# a124-vca.net
KiCad netlist of a schematic drawn in EAGLE
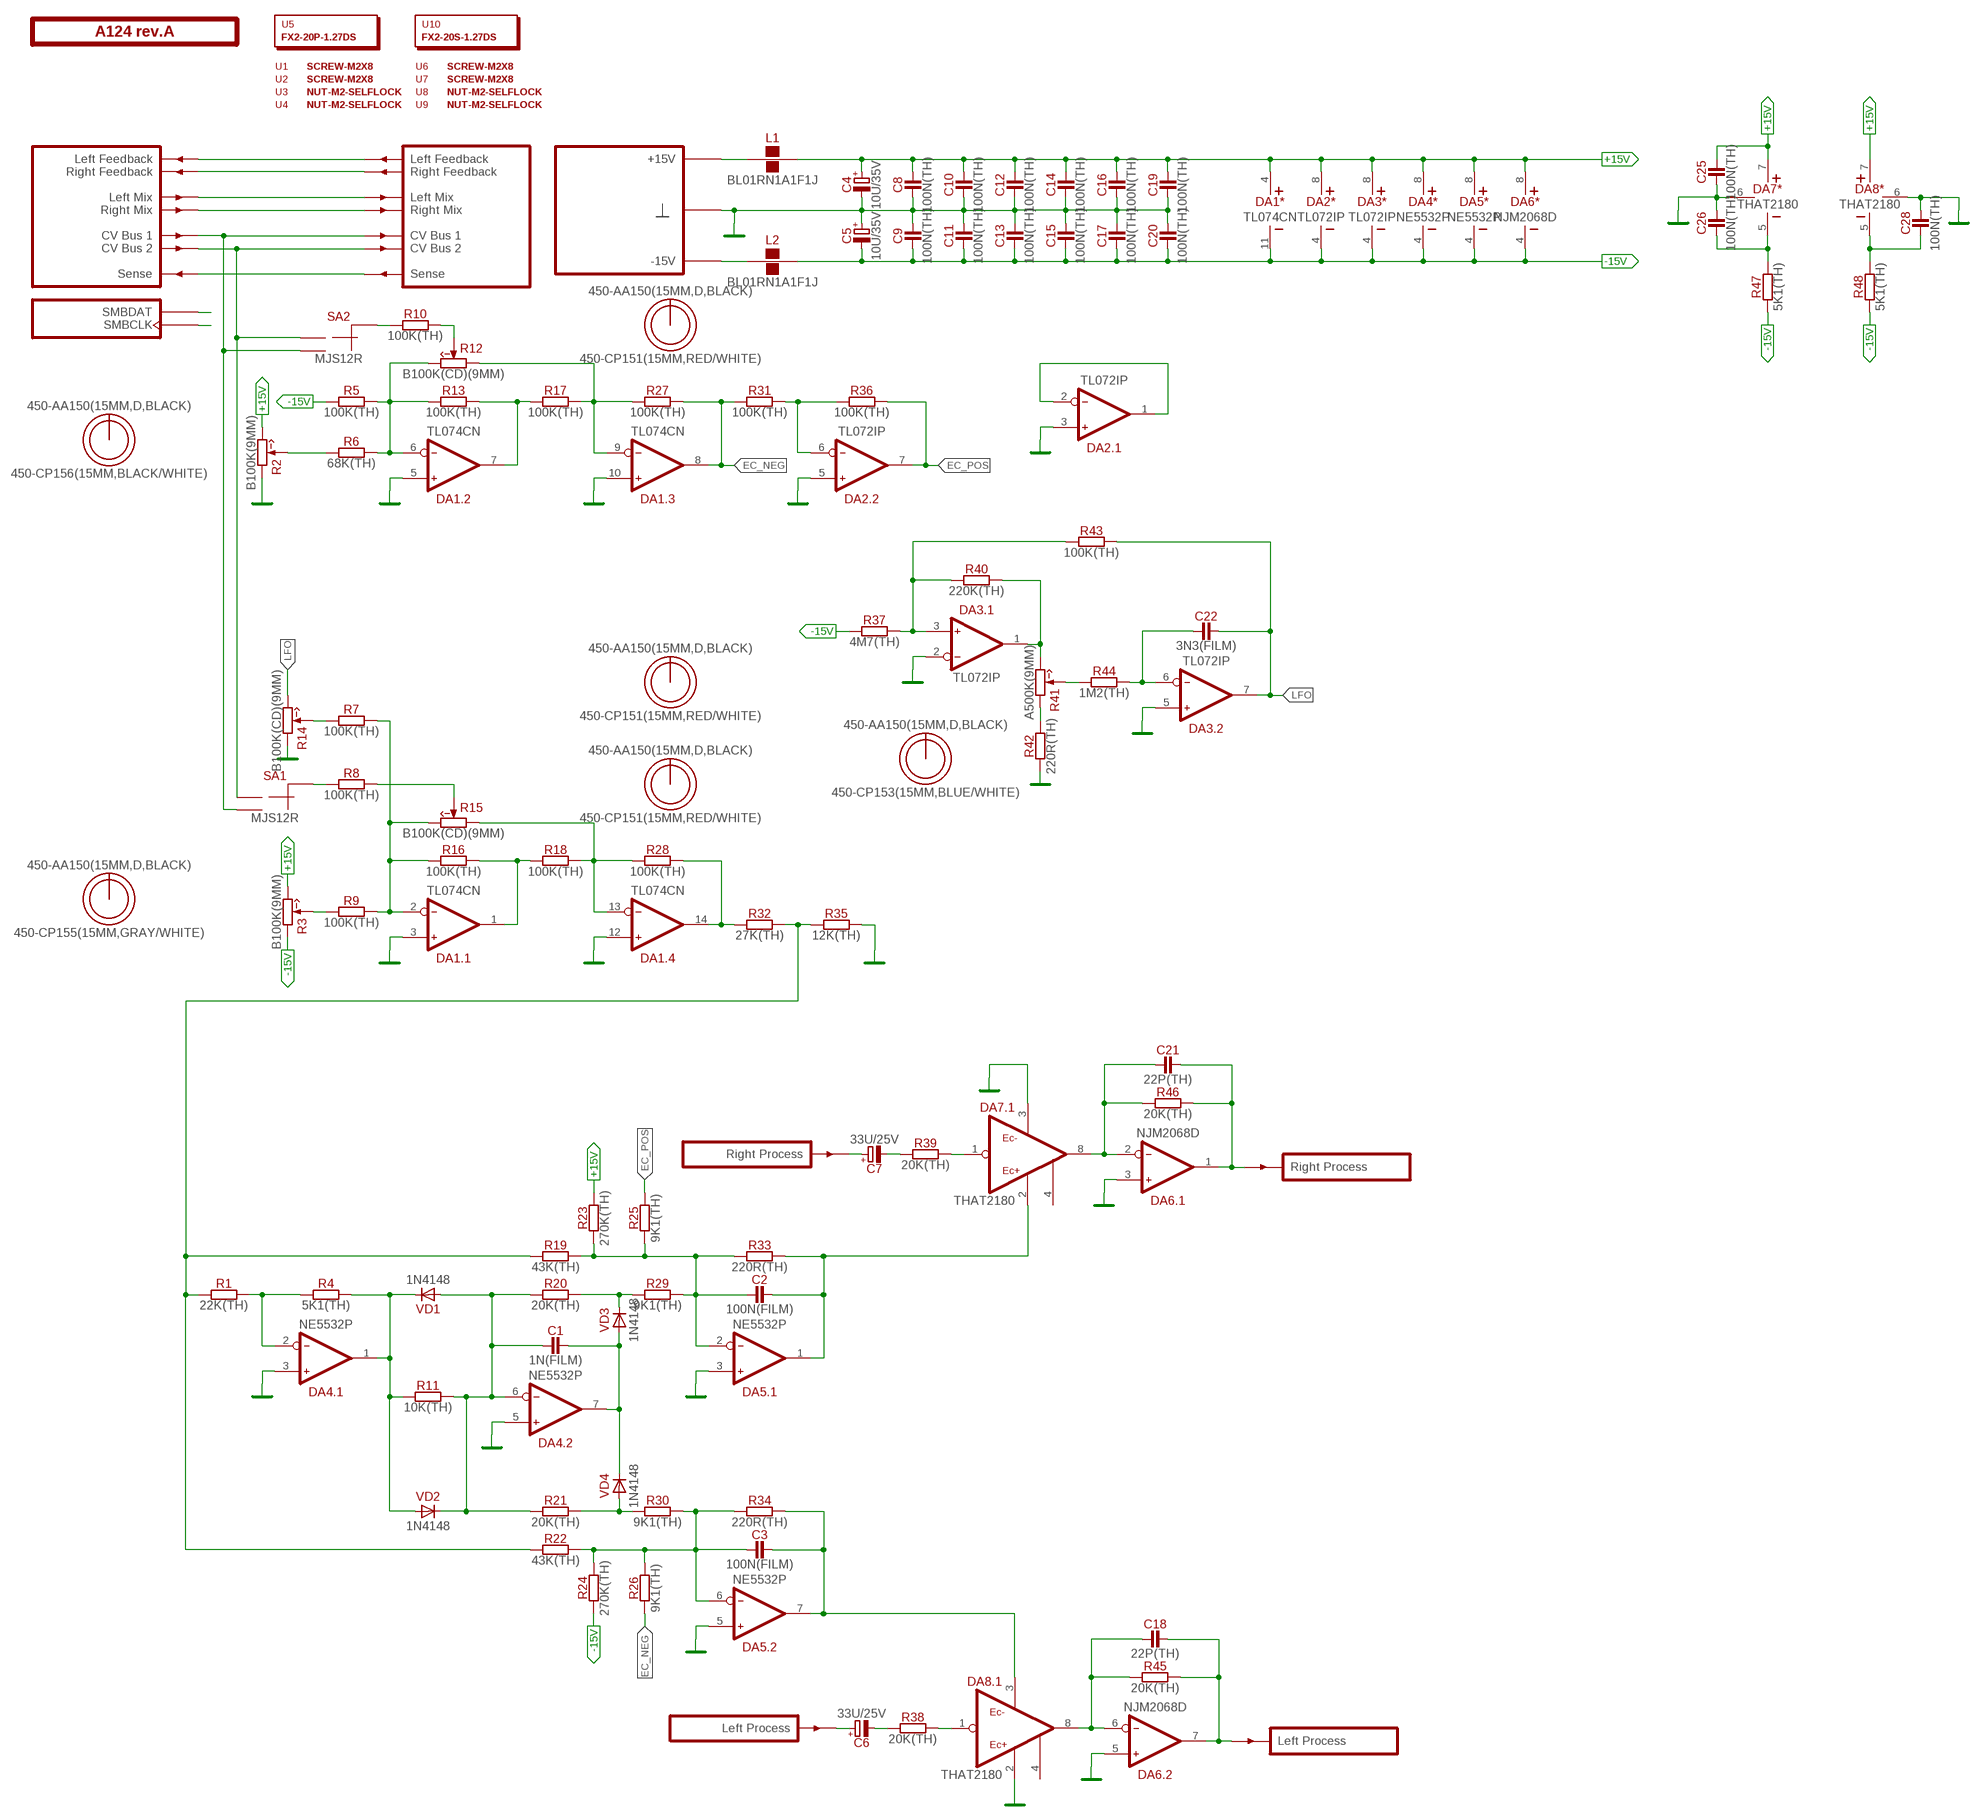
[diagram p0: schematic, sheet 1]

(export (version "E")
  (design (tool "Eeschema 10.0.6"))
  (components
    (comp (ref "C1")
      (value "1N(FILM)")
      (footprint "eagle-import:C050-025X075")
      (libsource (lib "eagle-import") (part "?1N(FILM)"))
    )
    (comp (ref "C2")
      (value "100N(FILM)")
      (footprint "eagle-import:C050-025X075")
      (libsource (lib "eagle-import") (part "?100N(FILM)"))
    )
    (comp (ref "C3")
      (value "100N(FILM)")
      (footprint "eagle-import:C050-025X075")
      (libsource (lib "eagle-import") (part "?100N(FILM)"))
    )
    (comp (ref "C4")
      (value "10U/35V")
      (footprint "eagle-import:E2-5")
      (libsource (lib "eagle-import") (part "?10U/35V"))
    )
    (comp (ref "C5")
      (value "10U/35V")
      (footprint "eagle-import:E2-5")
      (libsource (lib "eagle-import") (part "?10U/35V"))
    )
    (comp (ref "C6")
      (value "33U/25V")
      (footprint "eagle-import:E2,5-7")
      (libsource (lib "eagle-import") (part "?33U/25V"))
    )
    (comp (ref "C7")
      (value "33U/25V")
      (footprint "eagle-import:E2,5-7")
      (libsource (lib "eagle-import") (part "?33U/25V"))
    )
    (comp (ref "C8")
      (value "100N(TH)")
      (footprint "eagle-import:C050-024X044")
      (libsource (lib "eagle-import") (part "?100N(TH)"))
    )
    (comp (ref "C9")
      (value "100N(TH)")
      (footprint "eagle-import:C050-024X044")
      (libsource (lib "eagle-import") (part "?100N(TH)"))
    )
    (comp (ref "C10")
      (value "100N(TH)")
      (footprint "eagle-import:C050-024X044")
      (libsource (lib "eagle-import") (part "?100N(TH)"))
    )
    (comp (ref "C11")
      (value "100N(TH)")
      (footprint "eagle-import:C050-024X044")
      (libsource (lib "eagle-import") (part "?100N(TH)"))
    )
    (comp (ref "C12")
      (value "100N(TH)")
      (footprint "eagle-import:C050-024X044")
      (libsource (lib "eagle-import") (part "?100N(TH)"))
    )
    (comp (ref "C13")
      (value "100N(TH)")
      (footprint "eagle-import:C050-024X044")
      (libsource (lib "eagle-import") (part "?100N(TH)"))
    )
    (comp (ref "C14")
      (value "100N(TH)")
      (footprint "eagle-import:C050-024X044")
      (libsource (lib "eagle-import") (part "?100N(TH)"))
    )
    (comp (ref "C15")
      (value "100N(TH)")
      (footprint "eagle-import:C050-024X044")
      (libsource (lib "eagle-import") (part "?100N(TH)"))
    )
    (comp (ref "C16")
      (value "100N(TH)")
      (footprint "eagle-import:C050-024X044")
      (libsource (lib "eagle-import") (part "?100N(TH)"))
    )
    (comp (ref "C17")
      (value "100N(TH)")
      (footprint "eagle-import:C050-024X044")
      (libsource (lib "eagle-import") (part "?100N(TH)"))
    )
    (comp (ref "C18")
      (value "22P(TH)")
      (footprint "eagle-import:C050-024X044")
      (libsource (lib "eagle-import") (part "?22P(TH)"))
    )
    (comp (ref "C19")
      (value "100N(TH)")
      (footprint "eagle-import:C050-024X044")
      (libsource (lib "eagle-import") (part "?100N(TH)"))
    )
    (comp (ref "C20")
      (value "100N(TH)")
      (footprint "eagle-import:C050-024X044")
      (libsource (lib "eagle-import") (part "?100N(TH)"))
    )
    (comp (ref "C21")
      (value "22P(TH)")
      (footprint "eagle-import:C050-024X044")
      (libsource (lib "eagle-import") (part "?22P(TH)"))
    )
    (comp (ref "C22")
      (value "3N3(FILM)")
      (footprint "eagle-import:C050-025X075")
      (libsource (lib "eagle-import") (part "?3N3(FILM)"))
    )
    (comp (ref "C25")
      (value "100N(TH)")
      (footprint "eagle-import:C050-024X044")
      (libsource (lib "eagle-import") (part "?100N(TH)"))
    )
    (comp (ref "C26")
      (value "100N(TH)")
      (footprint "eagle-import:C050-024X044")
      (libsource (lib "eagle-import") (part "?100N(TH)"))
    )
    (comp (ref "C28")
      (value "100N(TH)")
      (footprint "eagle-import:C050-024X044")
      (libsource (lib "eagle-import") (part "?100N(TH)"))
    )
    (comp (ref "DA1")
      (value "TL074CN")
      (footprint "eagle-import:DIP-14")
      (libsource (lib "eagle-import") (part "TL074CN"))
    )
    (comp (ref "DA2")
      (value "TL072IP")
      (footprint "eagle-import:DIP-8")
      (libsource (lib "eagle-import") (part "TL072IP"))
    )
    (comp (ref "DA3")
      (value "TL072IP")
      (footprint "eagle-import:DIP-8")
      (libsource (lib "eagle-import") (part "TL072IP"))
    )
    (comp (ref "DA4")
      (value "NE5532P")
      (footprint "eagle-import:DIP-8")
      (libsource (lib "eagle-import") (part "NE5532P"))
    )
    (comp (ref "DA5")
      (value "NE5532P")
      (footprint "eagle-import:DIP-8")
      (libsource (lib "eagle-import") (part "NE5532P"))
    )
    (comp (ref "DA6")
      (value "NJM2068D")
      (footprint "eagle-import:DIP-8")
      (libsource (lib "eagle-import") (part "NJM2068D"))
    )
    (comp (ref "DA7")
      (value "THAT2180")
      (footprint "eagle-import:SIL8")
      (libsource (lib "eagle-import") (part "THAT2180"))
    )
    (comp (ref "DA8")
      (value "THAT2180")
      (footprint "eagle-import:SIL8")
      (libsource (lib "eagle-import") (part "THAT2180"))
    )
    (comp (ref "L1")
      (value "BL01RN1A1F1J")
      (footprint "eagle-import:BL01RN1A")
      (libsource (lib "eagle-import") (part "BL01RN1A?1F1J"))
    )
    (comp (ref "L2")
      (value "BL01RN1A1F1J")
      (footprint "eagle-import:BL01RN1A")
      (libsource (lib "eagle-import") (part "BL01RN1A?1F1J"))
    )
    (comp (ref "O1")
      (value "450-AA150(15MM,D,BLACK)")
      (footprint "eagle-import:EMPTY")
      (libsource (lib "eagle-import") (part "450-AA?150(15MM,D,BLACK)"))
    )
    (comp (ref "O2")
      (value "450-CP156(15MM,BLACK/WHITE)")
      (footprint "eagle-import:EMPTY")
      (libsource (lib "eagle-import") (part "450-C?P156(15MM,BLACK/WHITE)"))
    )
    (comp (ref "O3")
      (value "450-AA150(15MM,D,BLACK)")
      (footprint "eagle-import:EMPTY")
      (libsource (lib "eagle-import") (part "450-AA?150(15MM,D,BLACK)"))
    )
    (comp (ref "O4")
      (value "450-CP155(15MM,GRAY/WHITE)")
      (footprint "eagle-import:EMPTY")
      (libsource (lib "eagle-import") (part "450-C?P155(15MM,GRAY/WHITE)"))
    )
    (comp (ref "O5")
      (value "450-AA150(15MM,D,BLACK)")
      (footprint "eagle-import:EMPTY")
      (libsource (lib "eagle-import") (part "450-AA?150(15MM,D,BLACK)"))
    )
    (comp (ref "O6")
      (value "450-CP151(15MM,RED/WHITE)")
      (footprint "eagle-import:EMPTY")
      (libsource (lib "eagle-import") (part "450-C?P151(15MM,RED/WHITE)"))
    )
    (comp (ref "O7")
      (value "450-AA150(15MM,D,BLACK)")
      (footprint "eagle-import:EMPTY")
      (libsource (lib "eagle-import") (part "450-AA?150(15MM,D,BLACK)"))
    )
    (comp (ref "O8")
      (value "450-CP151(15MM,RED/WHITE)")
      (footprint "eagle-import:EMPTY")
      (libsource (lib "eagle-import") (part "450-C?P151(15MM,RED/WHITE)"))
    )
    (comp (ref "O9")
      (value "450-AA150(15MM,D,BLACK)")
      (footprint "eagle-import:EMPTY")
      (libsource (lib "eagle-import") (part "450-AA?150(15MM,D,BLACK)"))
    )
    (comp (ref "O10")
      (value "450-CP151(15MM,RED/WHITE)")
      (footprint "eagle-import:EMPTY")
      (libsource (lib "eagle-import") (part "450-C?P151(15MM,RED/WHITE)"))
    )
    (comp (ref "O11")
      (value "450-AA150(15MM,D,BLACK)")
      (footprint "eagle-import:EMPTY")
      (libsource (lib "eagle-import") (part "450-AA?150(15MM,D,BLACK)"))
    )
    (comp (ref "O12")
      (value "450-CP153(15MM,BLUE/WHITE)")
      (footprint "eagle-import:EMPTY")
      (libsource (lib "eagle-import") (part "450-C?P153(15MM,BLUE/WHITE)"))
    )
    (comp (ref "PCB1")
      (value "A124 rev.A")
      (footprint "eagle-import:ST2-BOARD-74")
      (libsource (lib "eagle-import") (part "ST2-BOARD-?74"))
    )
    (comp (ref "R1")
      (value "22K(TH)")
      (footprint "eagle-import:R-0207_10")
      (libsource (lib "eagle-import") (part "?22K(TH)"))
    )
    (comp (ref "R2")
      (value "B100K(9MM)")
      (footprint "eagle-import:RV09-SINGLE")
      (libsource (lib "eagle-import") (part "?B100K(9MM)"))
    )
    (comp (ref "R3")
      (value "B100K(9MM)")
      (footprint "eagle-import:RV09-SINGLE")
      (libsource (lib "eagle-import") (part "?B100K(9MM)"))
    )
    (comp (ref "R4")
      (value "5K1(TH)")
      (footprint "eagle-import:R-0207_10")
      (libsource (lib "eagle-import") (part "?5K1(TH)"))
    )
    (comp (ref "R5")
      (value "100K(TH)")
      (footprint "eagle-import:R-0207_10")
      (libsource (lib "eagle-import") (part "?100K(TH)"))
    )
    (comp (ref "R6")
      (value "68K(TH)")
      (footprint "eagle-import:R-0207_10")
      (libsource (lib "eagle-import") (part "?68K(TH)"))
    )
    (comp (ref "R7")
      (value "100K(TH)")
      (footprint "eagle-import:R-0207_10")
      (libsource (lib "eagle-import") (part "?100K(TH)"))
    )
    (comp (ref "R8")
      (value "100K(TH)")
      (footprint "eagle-import:R-0207_10")
      (libsource (lib "eagle-import") (part "?100K(TH)"))
    )
    (comp (ref "R9")
      (value "100K(TH)")
      (footprint "eagle-import:R-0207_10")
      (libsource (lib "eagle-import") (part "?100K(TH)"))
    )
    (comp (ref "R10")
      (value "100K(TH)")
      (footprint "eagle-import:R-0207_10")
      (libsource (lib "eagle-import") (part "?100K(TH)"))
    )
    (comp (ref "R11")
      (value "10K(TH)")
      (footprint "eagle-import:R-0207_10")
      (libsource (lib "eagle-import") (part "?10K(TH)"))
    )
    (comp (ref "R12")
      (value "B100K(CD)(9MM)")
      (footprint "eagle-import:RV09-SINGLE")
      (libsource (lib "eagle-import") (part "?B100K(CD)(9MM)"))
    )
    (comp (ref "R13")
      (value "100K(TH)")
      (footprint "eagle-import:R-0207_10")
      (libsource (lib "eagle-import") (part "?100K(TH)"))
    )
    (comp (ref "R14")
      (value "B100K(CD)(9MM)")
      (footprint "eagle-import:RV09-SINGLE")
      (libsource (lib "eagle-import") (part "?B100K(CD)(9MM)"))
    )
    (comp (ref "R15")
      (value "B100K(CD)(9MM)")
      (footprint "eagle-import:RV09-SINGLE")
      (libsource (lib "eagle-import") (part "?B100K(CD)(9MM)"))
    )
    (comp (ref "R16")
      (value "100K(TH)")
      (footprint "eagle-import:R-0207_10")
      (libsource (lib "eagle-import") (part "?100K(TH)"))
    )
    (comp (ref "R17")
      (value "100K(TH)")
      (footprint "eagle-import:R-0207_10")
      (libsource (lib "eagle-import") (part "?100K(TH)"))
    )
    (comp (ref "R18")
      (value "100K(TH)")
      (footprint "eagle-import:R-0207_10")
      (libsource (lib "eagle-import") (part "?100K(TH)"))
    )
    (comp (ref "R19")
      (value "43K(TH)")
      (footprint "eagle-import:R-0207_10")
      (libsource (lib "eagle-import") (part "?43K(TH)"))
    )
    (comp (ref "R20")
      (value "20K(TH)")
      (footprint "eagle-import:R-0207_10")
      (libsource (lib "eagle-import") (part "?20K(TH)"))
    )
    (comp (ref "R21")
      (value "20K(TH)")
      (footprint "eagle-import:R-0207_10")
      (libsource (lib "eagle-import") (part "?20K(TH)"))
    )
    (comp (ref "R22")
      (value "43K(TH)")
      (footprint "eagle-import:R-0207_10")
      (libsource (lib "eagle-import") (part "?43K(TH)"))
    )
    (comp (ref "R23")
      (value "270K(TH)")
      (footprint "eagle-import:R-0207_10")
      (libsource (lib "eagle-import") (part "?270K(TH)"))
    )
    (comp (ref "R24")
      (value "270K(TH)")
      (footprint "eagle-import:R-0207_10")
      (libsource (lib "eagle-import") (part "?270K(TH)"))
    )
    (comp (ref "R25")
      (value "9K1(TH)")
      (footprint "eagle-import:R-0207_10")
      (libsource (lib "eagle-import") (part "?9K1(TH)"))
    )
    (comp (ref "R26")
      (value "9K1(TH)")
      (footprint "eagle-import:R-0207_10")
      (libsource (lib "eagle-import") (part "?9K1(TH)"))
    )
    (comp (ref "R27")
      (value "100K(TH)")
      (footprint "eagle-import:R-0207_10")
      (libsource (lib "eagle-import") (part "?100K(TH)"))
    )
    (comp (ref "R28")
      (value "100K(TH)")
      (footprint "eagle-import:R-0207_10")
      (libsource (lib "eagle-import") (part "?100K(TH)"))
    )
    (comp (ref "R29")
      (value "9K1(TH)")
      (footprint "eagle-import:R-0207_10")
      (libsource (lib "eagle-import") (part "?9K1(TH)"))
    )
    (comp (ref "R30")
      (value "9K1(TH)")
      (footprint "eagle-import:R-0207_10")
      (libsource (lib "eagle-import") (part "?9K1(TH)"))
    )
    (comp (ref "R31")
      (value "100K(TH)")
      (footprint "eagle-import:R-0207_10")
      (libsource (lib "eagle-import") (part "?100K(TH)"))
    )
    (comp (ref "R32")
      (value "27K(TH)")
      (footprint "eagle-import:R-0207_10")
      (libsource (lib "eagle-import") (part "?27K(TH)"))
    )
    (comp (ref "R33")
      (value "220R(TH)")
      (footprint "eagle-import:R-0207_10")
      (libsource (lib "eagle-import") (part "?220R(TH)"))
    )
    (comp (ref "R34")
      (value "220R(TH)")
      (footprint "eagle-import:R-0207_10")
      (libsource (lib "eagle-import") (part "?220R(TH)"))
    )
    (comp (ref "R35")
      (value "12K(TH)")
      (footprint "eagle-import:R-0207_10")
      (libsource (lib "eagle-import") (part "?12K(TH)"))
    )
    (comp (ref "R36")
      (value "100K(TH)")
      (footprint "eagle-import:R-0207_10")
      (libsource (lib "eagle-import") (part "?100K(TH)"))
    )
    (comp (ref "R37")
      (value "4M7(TH)")
      (footprint "eagle-import:R-0207_10")
      (libsource (lib "eagle-import") (part "?4M7(TH)"))
    )
    (comp (ref "R38")
      (value "20K(TH)")
      (footprint "eagle-import:R-0207_10")
      (libsource (lib "eagle-import") (part "?20K(TH)"))
    )
    (comp (ref "R39")
      (value "20K(TH)")
      (footprint "eagle-import:R-0207_10")
      (libsource (lib "eagle-import") (part "?20K(TH)"))
    )
    (comp (ref "R40")
      (value "220K(TH)")
      (footprint "eagle-import:R-0207_10")
      (libsource (lib "eagle-import") (part "?220K(TH)"))
    )
    (comp (ref "R41")
      (value "A500K(9MM)")
      (footprint "eagle-import:RV09-SINGLE")
      (libsource (lib "eagle-import") (part "?A500K(9MM)"))
    )
    (comp (ref "R42")
      (value "220R(TH)")
      (footprint "eagle-import:R-0207_10")
      (libsource (lib "eagle-import") (part "?220R(TH)"))
    )
    (comp (ref "R43")
      (value "100K(TH)")
      (footprint "eagle-import:R-0207_10")
      (libsource (lib "eagle-import") (part "?100K(TH)"))
    )
    (comp (ref "R44")
      (value "1M2(TH)")
      (footprint "eagle-import:R-0207_10")
      (libsource (lib "eagle-import") (part "?1M2(TH)"))
    )
    (comp (ref "R45")
      (value "20K(TH)")
      (footprint "eagle-import:R-0207_10")
      (libsource (lib "eagle-import") (part "?20K(TH)"))
    )
    (comp (ref "R46")
      (value "20K(TH)")
      (footprint "eagle-import:R-0207_10")
      (libsource (lib "eagle-import") (part "?20K(TH)"))
    )
    (comp (ref "R47")
      (value "5K1(TH)")
      (footprint "eagle-import:R-0207_10")
      (libsource (lib "eagle-import") (part "?5K1(TH)"))
    )
    (comp (ref "R48")
      (value "5K1(TH)")
      (footprint "eagle-import:R-0207_10")
      (libsource (lib "eagle-import") (part "?5K1(TH)"))
    )
    (comp (ref "SA1")
      (value "MJS12R")
      (footprint "eagle-import:APEM-MJS12R")
      (libsource (lib "eagle-import") (part "MJS12R"))
    )
    (comp (ref "SA2")
      (value "MJS12R")
      (footprint "eagle-import:APEM-MJS12R")
      (libsource (lib "eagle-import") (part "MJS12R"))
    )
    (comp (ref "U1")
      (value "SCREW-M2X8")
      (footprint "eagle-import:EMPTY")
      (libsource (lib "eagle-import") (part "?SCREW-M2X8"))
    )
    (comp (ref "U2")
      (value "SCREW-M2X8")
      (footprint "eagle-import:EMPTY")
      (libsource (lib "eagle-import") (part "?SCREW-M2X8"))
    )
    (comp (ref "U3")
      (value "NUT-M2-SELFLOCK")
      (footprint "eagle-import:EMPTY")
      (libsource (lib "eagle-import") (part "?NUT-M2-SELFLOCK"))
    )
    (comp (ref "U4")
      (value "NUT-M2-SELFLOCK")
      (footprint "eagle-import:EMPTY")
      (libsource (lib "eagle-import") (part "?NUT-M2-SELFLOCK"))
    )
    (comp (ref "U5")
      (value "FX2-20P-1.27DS")
      (footprint "eagle-import:EMPTY")
      (libsource (lib "eagle-import") (part "?FX2-20P-1.27DS"))
    )
    (comp (ref "U6")
      (value "SCREW-M2X8")
      (footprint "eagle-import:EMPTY")
      (libsource (lib "eagle-import") (part "?SCREW-M2X8"))
    )
    (comp (ref "U7")
      (value "SCREW-M2X8")
      (footprint "eagle-import:EMPTY")
      (libsource (lib "eagle-import") (part "?SCREW-M2X8"))
    )
    (comp (ref "U8")
      (value "NUT-M2-SELFLOCK")
      (footprint "eagle-import:EMPTY")
      (libsource (lib "eagle-import") (part "?NUT-M2-SELFLOCK"))
    )
    (comp (ref "U9")
      (value "NUT-M2-SELFLOCK")
      (footprint "eagle-import:EMPTY")
      (libsource (lib "eagle-import") (part "?NUT-M2-SELFLOCK"))
    )
    (comp (ref "U10")
      (value "FX2-20S-1.27DS")
      (footprint "eagle-import:EMPTY")
      (libsource (lib "eagle-import") (part "?FX2-20S-1.27DS"))
    )
    (comp (ref "VD1")
      (value "1N4148")
      (footprint "eagle-import:DO35-7")
      (libsource (lib "eagle-import") (part "?1N4148"))
    )
    (comp (ref "VD2")
      (value "1N4148")
      (footprint "eagle-import:DO35-7")
      (libsource (lib "eagle-import") (part "?1N4148"))
    )
    (comp (ref "VD3")
      (value "1N4148")
      (footprint "eagle-import:DO35-7")
      (libsource (lib "eagle-import") (part "?1N4148"))
    )
    (comp (ref "VD4")
      (value "1N4148")
      (footprint "eagle-import:DO35-7")
      (libsource (lib "eagle-import") (part "?1N4148"))
    )
  )
  (nets
    (net (code "1") (name "+15V") (class "Default")
      (node (ref "C10") (pin "2") (pinfunction "2_2") (pintype "passive"))
      (node (ref "C12") (pin "2") (pinfunction "2_2") (pintype "passive"))
      (node (ref "C14") (pin "2") (pinfunction "2_2") (pintype "passive"))
      (node (ref "C16") (pin "2") (pinfunction "2_2") (pintype "passive"))
      (node (ref "C19") (pin "2") (pinfunction "2_2") (pintype "passive"))
      (node (ref "C25") (pin "2") (pinfunction "2_2") (pintype "passive"))
      (node (ref "C4") (pin "+") (pinfunction "+_+") (pintype "passive"))
      (node (ref "C8") (pin "2") (pinfunction "2_2") (pintype "passive"))
      (node (ref "DA1") (pin "4") (pinfunction "V+_4") (pintype "power_in"))
      (node (ref "DA2") (pin "8") (pinfunction "V+_8") (pintype "power_in"))
      (node (ref "DA3") (pin "8") (pinfunction "V+_8") (pintype "power_in"))
      (node (ref "DA4") (pin "8") (pinfunction "V+_8") (pintype "power_in"))
      (node (ref "DA5") (pin "8") (pinfunction "V+_8") (pintype "power_in"))
      (node (ref "DA6") (pin "8") (pinfunction "V+_8") (pintype "power_in"))
      (node (ref "DA7") (pin "7") (pinfunction "V+_7") (pintype "power_in"))
      (node (ref "DA8") (pin "7") (pinfunction "V+_7") (pintype "power_in"))
      (node (ref "L1") (pin "2") (pinfunction "2_2") (pintype "passive"))
      (node (ref "R2") (pin "3") (pinfunction "CW_3") (pintype "passive"))
      (node (ref "R23") (pin "2") (pinfunction "2_2") (pintype "passive"))
      (node (ref "R3") (pin "3") (pinfunction "CW_3") (pintype "passive"))
    )
    (net (code "2") (name "-15V") (class "Default")
      (node (ref "C11") (pin "1") (pinfunction "1_1") (pintype "passive"))
      (node (ref "C13") (pin "1") (pinfunction "1_1") (pintype "passive"))
      (node (ref "C15") (pin "1") (pinfunction "1_1") (pintype "passive"))
      (node (ref "C17") (pin "1") (pinfunction "1_1") (pintype "passive"))
      (node (ref "C20") (pin "1") (pinfunction "1_1") (pintype "passive"))
      (node (ref "C5") (pin "-") (pinfunction "-_-") (pintype "passive"))
      (node (ref "C9") (pin "1") (pinfunction "1_1") (pintype "passive"))
      (node (ref "DA1") (pin "11") (pinfunction "V-_11") (pintype "power_in"))
      (node (ref "DA2") (pin "4") (pinfunction "V-_4") (pintype "power_in"))
      (node (ref "DA3") (pin "4") (pinfunction "V-_4") (pintype "power_in"))
      (node (ref "DA4") (pin "4") (pinfunction "V-_4") (pintype "power_in"))
      (node (ref "DA5") (pin "4") (pinfunction "V-_4") (pintype "power_in"))
      (node (ref "DA6") (pin "4") (pinfunction "V-_4") (pintype "power_in"))
      (node (ref "L2") (pin "2") (pinfunction "2_2") (pintype "passive"))
      (node (ref "R24") (pin "1") (pinfunction "1_1") (pintype "passive"))
      (node (ref "R3") (pin "1") (pinfunction "CCW_1") (pintype "passive"))
      (node (ref "R37") (pin "1") (pinfunction "1_1") (pintype "passive"))
      (node (ref "R47") (pin "1") (pinfunction "1_1") (pintype "passive"))
      (node (ref "R48") (pin "1") (pinfunction "1_1") (pintype "passive"))
      (node (ref "R5") (pin "1") (pinfunction "1_1") (pintype "passive"))
    )
    (net (code "3") (name "EC_NEG") (class "Default")
      (node (ref "DA1") (pin "8") (pinfunction "OUT_8") (pintype "output"))
      (node (ref "R26") (pin "1") (pinfunction "1_1") (pintype "passive"))
      (node (ref "R27") (pin "2") (pinfunction "2_2") (pintype "passive"))
      (node (ref "R31") (pin "1") (pinfunction "1_1") (pintype "passive"))
    )
    (net (code "4") (name "EC_POS") (class "Default")
      (node (ref "DA2") (pin "7") (pinfunction "OUT_7") (pintype "output"))
      (node (ref "R25") (pin "2") (pinfunction "2_2") (pintype "passive"))
      (node (ref "R36") (pin "2") (pinfunction "2_2") (pintype "passive"))
    )
    (net (code "5") (name "GND") (class "Default")
      (node (ref "C10") (pin "1") (pinfunction "1_1") (pintype "passive"))
      (node (ref "C11") (pin "2") (pinfunction "2_2") (pintype "passive"))
      (node (ref "C12") (pin "1") (pinfunction "1_1") (pintype "passive"))
      (node (ref "C13") (pin "2") (pinfunction "2_2") (pintype "passive"))
      (node (ref "C14") (pin "1") (pinfunction "1_1") (pintype "passive"))
      (node (ref "C15") (pin "2") (pinfunction "2_2") (pintype "passive"))
      (node (ref "C16") (pin "1") (pinfunction "1_1") (pintype "passive"))
      (node (ref "C17") (pin "2") (pinfunction "2_2") (pintype "passive"))
      (node (ref "C19") (pin "1") (pinfunction "1_1") (pintype "passive"))
      (node (ref "C20") (pin "2") (pinfunction "2_2") (pintype "passive"))
      (node (ref "C25") (pin "1") (pinfunction "1_1") (pintype "passive"))
      (node (ref "C26") (pin "2") (pinfunction "2_2") (pintype "passive"))
      (node (ref "C28") (pin "2") (pinfunction "2_2") (pintype "passive"))
      (node (ref "C4") (pin "-") (pinfunction "-_-") (pintype "passive"))
      (node (ref "C5") (pin "+") (pinfunction "+_+") (pintype "passive"))
      (node (ref "C8") (pin "1") (pinfunction "1_1") (pintype "passive"))
      (node (ref "C9") (pin "2") (pinfunction "2_2") (pintype "passive"))
      (node (ref "DA1") (pin "10") (pinfunction "IN+_10") (pintype "input"))
      (node (ref "DA1") (pin "12") (pinfunction "IN+_12") (pintype "input"))
      (node (ref "DA1") (pin "3") (pinfunction "IN+_3") (pintype "input"))
      (node (ref "DA1") (pin "5") (pinfunction "IN+_5") (pintype "input"))
      (node (ref "DA2") (pin "3") (pinfunction "IN+_3") (pintype "input"))
      (node (ref "DA2") (pin "5") (pinfunction "IN+_5") (pintype "input"))
      (node (ref "DA3") (pin "2") (pinfunction "IN-_2") (pintype "input"))
      (node (ref "DA3") (pin "5") (pinfunction "IN+_5") (pintype "input"))
      (node (ref "DA4") (pin "3") (pinfunction "IN+_3") (pintype "input"))
      (node (ref "DA4") (pin "5") (pinfunction "IN+_5") (pintype "input"))
      (node (ref "DA5") (pin "3") (pinfunction "IN+_3") (pintype "input"))
      (node (ref "DA5") (pin "5") (pinfunction "IN+_5") (pintype "input"))
      (node (ref "DA6") (pin "3") (pinfunction "IN+_3") (pintype "input"))
      (node (ref "DA6") (pin "5") (pinfunction "IN+_5") (pintype "input"))
      (node (ref "DA7") (pin "3") (pinfunction "EC-_3") (pintype "output"))
      (node (ref "DA7") (pin "6") (pinfunction "GND_6") (pintype "power_in"))
      (node (ref "DA8") (pin "2") (pinfunction "EC+_2") (pintype "output"))
      (node (ref "DA8") (pin "6") (pinfunction "GND_6") (pintype "power_in"))
      (node (ref "PCB1") (pin "B4") (pinfunction "GND_B4") (pintype "bidirectional"))
      (node (ref "PCB1") (pin "B4'") (pinfunction "GND_B4'") (pintype "bidirectional"))
      (node (ref "PCB1") (pin "B5") (pinfunction "GND_B5") (pintype "bidirectional"))
      (node (ref "PCB1") (pin "B5'") (pinfunction "GND_B5'") (pintype "bidirectional"))
      (node (ref "PCB1") (pin "B6") (pinfunction "GND_B6") (pintype "bidirectional"))
      (node (ref "PCB1") (pin "B6'") (pinfunction "GND_B6'") (pintype "bidirectional"))
      (node (ref "PCB1") (pin "B7") (pinfunction "GND_B7") (pintype "bidirectional"))
      (node (ref "PCB1") (pin "B7'") (pinfunction "GND_B7'") (pintype "bidirectional"))
      (node (ref "PCB1") (pin "B8") (pinfunction "GND_B8") (pintype "bidirectional"))
      (node (ref "PCB1") (pin "B8'") (pinfunction "GND_B8'") (pintype "bidirectional"))
      (node (ref "R14") (pin "1") (pinfunction "CCW_1") (pintype "passive"))
      (node (ref "R2") (pin "1") (pinfunction "CCW_1") (pintype "passive"))
      (node (ref "R35") (pin "2") (pinfunction "2_2") (pintype "passive"))
      (node (ref "R42") (pin "1") (pinfunction "1_1") (pintype "passive"))
    )
    (net (code "6") (name "LFO") (class "Default")
      (node (ref "C22") (pin "2") (pinfunction "2_2") (pintype "passive"))
      (node (ref "DA3") (pin "7") (pinfunction "OUT_7") (pintype "output"))
      (node (ref "R14") (pin "3") (pinfunction "CW_3") (pintype "passive"))
      (node (ref "R43") (pin "2") (pinfunction "2_2") (pintype "passive"))
    )
    (net (code "7") (name "Net-(C6-Pad-)") (class "Default")
      (node (ref "C6") (pin "-") (pinfunction "-_-") (pintype "passive"))
      (node (ref "R38") (pin "1") (pinfunction "1_1") (pintype "passive"))
    )
    (net (code "8") (name "Net-(C7-Pad-)") (class "Default")
      (node (ref "C7") (pin "-") (pinfunction "-_-") (pintype "passive"))
      (node (ref "R39") (pin "1") (pinfunction "1_1") (pintype "passive"))
    )
    (net (code "9") (name "Net-(DA1B-IN-)") (class "Default")
      (node (ref "DA1") (pin "2") (pinfunction "IN-_2") (pintype "input"))
      (node (ref "R15") (pin "3") (pinfunction "CW_3") (pintype "passive"))
      (node (ref "R16") (pin "1") (pinfunction "1_1") (pintype "passive"))
      (node (ref "R7") (pin "2") (pinfunction "2_2") (pintype "passive"))
      (node (ref "R9") (pin "2") (pinfunction "2_2") (pintype "passive"))
    )
    (net (code "10") (name "Net-(DA1B-OUT)") (class "Default")
      (node (ref "DA1") (pin "1") (pinfunction "OUT_1") (pintype "output"))
      (node (ref "R16") (pin "2") (pinfunction "2_2") (pintype "passive"))
      (node (ref "R18") (pin "1") (pinfunction "1_1") (pintype "passive"))
    )
    (net (code "11") (name "Net-(DA1C-IN-)") (class "Default")
      (node (ref "DA1") (pin "6") (pinfunction "IN-_6") (pintype "input"))
      (node (ref "R12") (pin "3") (pinfunction "CW_3") (pintype "passive"))
      (node (ref "R13") (pin "1") (pinfunction "1_1") (pintype "passive"))
      (node (ref "R5") (pin "2") (pinfunction "2_2") (pintype "passive"))
      (node (ref "R6") (pin "2") (pinfunction "2_2") (pintype "passive"))
    )
    (net (code "12") (name "Net-(DA1C-OUT)") (class "Default")
      (node (ref "DA1") (pin "7") (pinfunction "OUT_7") (pintype "output"))
      (node (ref "R13") (pin "2") (pinfunction "2_2") (pintype "passive"))
      (node (ref "R17") (pin "1") (pinfunction "1_1") (pintype "passive"))
    )
    (net (code "13") (name "Net-(DA1D-IN-)") (class "Default")
      (node (ref "DA1") (pin "9") (pinfunction "IN-_9") (pintype "input"))
      (node (ref "R12") (pin "1") (pinfunction "CCW_1") (pintype "passive"))
      (node (ref "R17") (pin "2") (pinfunction "2_2") (pintype "passive"))
      (node (ref "R27") (pin "1") (pinfunction "1_1") (pintype "passive"))
    )
    (net (code "14") (name "Net-(DA1E-IN-)") (class "Default")
      (node (ref "DA1") (pin "13") (pinfunction "IN-_13") (pintype "input"))
      (node (ref "R15") (pin "1") (pinfunction "CCW_1") (pintype "passive"))
      (node (ref "R18") (pin "2") (pinfunction "2_2") (pintype "passive"))
      (node (ref "R28") (pin "1") (pinfunction "1_1") (pintype "passive"))
    )
    (net (code "15") (name "Net-(DA1E-OUT)") (class "Default")
      (node (ref "DA1") (pin "14") (pinfunction "OUT_14") (pintype "output"))
      (node (ref "R28") (pin "2") (pinfunction "2_2") (pintype "passive"))
      (node (ref "R32") (pin "1") (pinfunction "1_1") (pintype "passive"))
    )
    (net (code "16") (name "Net-(DA2B-IN-)") (class "Default")
      (node (ref "DA2") (pin "1") (pinfunction "OUT_1") (pintype "output"))
      (node (ref "DA2") (pin "2") (pinfunction "IN-_2") (pintype "input"))
    )
    (net (code "17") (name "Net-(DA2C-IN-)") (class "Default")
      (node (ref "DA2") (pin "6") (pinfunction "IN-_6") (pintype "input"))
      (node (ref "R31") (pin "2") (pinfunction "2_2") (pintype "passive"))
      (node (ref "R36") (pin "1") (pinfunction "1_1") (pintype "passive"))
    )
    (net (code "18") (name "Net-(DA3B-IN+)") (class "Default")
      (node (ref "DA3") (pin "3") (pinfunction "IN+_3") (pintype "input"))
      (node (ref "R37") (pin "2") (pinfunction "2_2") (pintype "passive"))
      (node (ref "R40") (pin "1") (pinfunction "1_1") (pintype "passive"))
      (node (ref "R43") (pin "1") (pinfunction "1_1") (pintype "passive"))
    )
    (net (code "19") (name "Net-(DA3B-OUT)") (class "Default")
      (node (ref "DA3") (pin "1") (pinfunction "OUT_1") (pintype "output"))
      (node (ref "R40") (pin "2") (pinfunction "2_2") (pintype "passive"))
      (node (ref "R41") (pin "3") (pinfunction "CW_3") (pintype "passive"))
    )
    (net (code "20") (name "Net-(DA3C-IN-)") (class "Default")
      (node (ref "C22") (pin "1") (pinfunction "1_1") (pintype "passive"))
      (node (ref "DA3") (pin "6") (pinfunction "IN-_6") (pintype "input"))
      (node (ref "R44") (pin "2") (pinfunction "2_2") (pintype "passive"))
    )
    (net (code "21") (name "Net-(DA4B-IN-)") (class "Default")
      (node (ref "DA4") (pin "2") (pinfunction "IN-_2") (pintype "input"))
      (node (ref "R1") (pin "2") (pinfunction "2_2") (pintype "passive"))
      (node (ref "R4") (pin "1") (pinfunction "1_1") (pintype "passive"))
    )
    (net (code "22") (name "Net-(DA4B-OUT)") (class "Default")
      (node (ref "DA4") (pin "1") (pinfunction "OUT_1") (pintype "output"))
      (node (ref "R11") (pin "1") (pinfunction "1_1") (pintype "passive"))
      (node (ref "R4") (pin "2") (pinfunction "2_2") (pintype "passive"))
      (node (ref "VD1") (pin "C") (pinfunction "C_C") (pintype "passive"))
      (node (ref "VD2") (pin "A") (pinfunction "A_A") (pintype "passive"))
    )
    (net (code "23") (name "Net-(DA4C-IN-)") (class "Default")
      (node (ref "C1") (pin "1") (pinfunction "1_1") (pintype "passive"))
      (node (ref "DA4") (pin "6") (pinfunction "IN-_6") (pintype "input"))
      (node (ref "R11") (pin "2") (pinfunction "2_2") (pintype "passive"))
      (node (ref "R20") (pin "1") (pinfunction "1_1") (pintype "passive"))
      (node (ref "R21") (pin "1") (pinfunction "1_1") (pintype "passive"))
      (node (ref "VD1") (pin "A") (pinfunction "A_A") (pintype "passive"))
      (node (ref "VD2") (pin "C") (pinfunction "C_C") (pintype "passive"))
    )
    (net (code "24") (name "Net-(DA4C-OUT)") (class "Default")
      (node (ref "C1") (pin "2") (pinfunction "2_2") (pintype "passive"))
      (node (ref "DA4") (pin "7") (pinfunction "OUT_7") (pintype "output"))
      (node (ref "VD3") (pin "A") (pinfunction "A_A") (pintype "passive"))
      (node (ref "VD4") (pin "C") (pinfunction "C_C") (pintype "passive"))
    )
    (net (code "25") (name "Net-(DA5B-IN-)") (class "Default")
      (node (ref "C2") (pin "1") (pinfunction "1_1") (pintype "passive"))
      (node (ref "DA5") (pin "2") (pinfunction "IN-_2") (pintype "input"))
      (node (ref "R19") (pin "2") (pinfunction "2_2") (pintype "passive"))
      (node (ref "R23") (pin "1") (pinfunction "1_1") (pintype "passive"))
      (node (ref "R25") (pin "1") (pinfunction "1_1") (pintype "passive"))
      (node (ref "R29") (pin "2") (pinfunction "2_2") (pintype "passive"))
      (node (ref "R33") (pin "1") (pinfunction "1_1") (pintype "passive"))
    )
    (net (code "26") (name "Net-(DA5B-OUT)") (class "Default")
      (node (ref "C2") (pin "2") (pinfunction "2_2") (pintype "passive"))
      (node (ref "DA5") (pin "1") (pinfunction "OUT_1") (pintype "output"))
      (node (ref "DA7") (pin "2") (pinfunction "EC+_2") (pintype "output"))
      (node (ref "R33") (pin "2") (pinfunction "2_2") (pintype "passive"))
    )
    (net (code "27") (name "Net-(DA5C-IN-)") (class "Default")
      (node (ref "C3") (pin "1") (pinfunction "1_1") (pintype "passive"))
      (node (ref "DA5") (pin "6") (pinfunction "IN-_6") (pintype "input"))
      (node (ref "R22") (pin "2") (pinfunction "2_2") (pintype "passive"))
      (node (ref "R24") (pin "2") (pinfunction "2_2") (pintype "passive"))
      (node (ref "R26") (pin "2") (pinfunction "2_2") (pintype "passive"))
      (node (ref "R30") (pin "2") (pinfunction "2_2") (pintype "passive"))
      (node (ref "R34") (pin "1") (pinfunction "1_1") (pintype "passive"))
    )
    (net (code "28") (name "Net-(DA5C-OUT)") (class "Default")
      (node (ref "C3") (pin "2") (pinfunction "2_2") (pintype "passive"))
      (node (ref "DA5") (pin "7") (pinfunction "OUT_7") (pintype "output"))
      (node (ref "DA8") (pin "3") (pinfunction "EC-_3") (pintype "output"))
      (node (ref "R34") (pin "2") (pinfunction "2_2") (pintype "passive"))
    )
    (net (code "29") (name "Net-(DA6B-IN-)") (class "Default")
      (node (ref "C21") (pin "1") (pinfunction "1_1") (pintype "passive"))
      (node (ref "DA6") (pin "2") (pinfunction "IN-_2") (pintype "input"))
      (node (ref "DA7") (pin "8") (pinfunction "OUT_8") (pintype "output"))
      (node (ref "R46") (pin "1") (pinfunction "1_1") (pintype "passive"))
    )
    (net (code "30") (name "Net-(DA6B-OUT)") (class "Default")
      (node (ref "C21") (pin "2") (pinfunction "2_2") (pintype "passive"))
      (node (ref "DA6") (pin "1") (pinfunction "OUT_1") (pintype "output"))
      (node (ref "PCB1") (pin "BOUTR'") (pinfunction "OUTR_BOUTR'") (pintype "bidirectional"))
      (node (ref "R46") (pin "2") (pinfunction "2_2") (pintype "passive"))
    )
    (net (code "31") (name "Net-(DA6C-IN-)") (class "Default")
      (node (ref "C18") (pin "1") (pinfunction "1_1") (pintype "passive"))
      (node (ref "DA6") (pin "6") (pinfunction "IN-_6") (pintype "input"))
      (node (ref "DA8") (pin "8") (pinfunction "OUT_8") (pintype "output"))
      (node (ref "R45") (pin "1") (pinfunction "1_1") (pintype "passive"))
    )
    (net (code "32") (name "Net-(DA6C-OUT)") (class "Default")
      (node (ref "C18") (pin "2") (pinfunction "2_2") (pintype "passive"))
      (node (ref "DA6") (pin "7") (pinfunction "OUT_7") (pintype "output"))
      (node (ref "PCB1") (pin "BOUTL'") (pinfunction "OUTL_BOUTL'") (pintype "bidirectional"))
      (node (ref "R45") (pin "2") (pinfunction "2_2") (pintype "passive"))
    )
    (net (code "33") (name "Net-(DA7A-V-)") (class "Default")
      (node (ref "C26") (pin "1") (pinfunction "1_1") (pintype "passive"))
      (node (ref "DA7") (pin "5") (pinfunction "V-_5") (pintype "power_in"))
      (node (ref "R47") (pin "2") (pinfunction "2_2") (pintype "passive"))
    )
    (net (code "34") (name "Net-(DA7B-IN-)") (class "Default")
      (node (ref "DA7") (pin "1") (pinfunction "IN-_1") (pintype "input"))
      (node (ref "R39") (pin "2") (pinfunction "2_2") (pintype "passive"))
    )
    (net (code "35") (name "Net-(DA8A-V-)") (class "Default")
      (node (ref "C28") (pin "1") (pinfunction "1_1") (pintype "passive"))
      (node (ref "DA8") (pin "5") (pinfunction "V-_5") (pintype "power_in"))
      (node (ref "R48") (pin "2") (pinfunction "2_2") (pintype "passive"))
    )
    (net (code "36") (name "Net-(DA8B-IN-)") (class "Default")
      (node (ref "DA8") (pin "1") (pinfunction "IN-_1") (pintype "input"))
      (node (ref "R38") (pin "2") (pinfunction "2_2") (pintype "passive"))
    )
    (net (code "37") (name "Net-(L1-Pad1)") (class "Default")
      (node (ref "L1") (pin "1") (pinfunction "1_1") (pintype "passive"))
      (node (ref "PCB1") (pin "A+15") (pinfunction "P+15V_A+15") (pintype "bidirectional"))
      (node (ref "PCB1") (pin "A+15'") (pinfunction "P+15V_A+15'") (pintype "bidirectional"))
      (node (ref "PCB1") (pin "B+15") (pinfunction "P+15V_B+15") (pintype "bidirectional"))
      (node (ref "PCB1") (pin "B+15'") (pinfunction "P+15V_B+15'") (pintype "bidirectional"))
    )
    (net (code "38") (name "Net-(L2-Pad1)") (class "Default")
      (node (ref "L2") (pin "1") (pinfunction "1_1") (pintype "passive"))
      (node (ref "PCB1") (pin "A-15") (pinfunction "P-15V_A-15") (pintype "bidirectional"))
      (node (ref "PCB1") (pin "A-15'") (pinfunction "P-15V_A-15'") (pintype "bidirectional"))
      (node (ref "PCB1") (pin "B-15") (pinfunction "P-15V_B-15") (pintype "bidirectional"))
      (node (ref "PCB1") (pin "B-15'") (pinfunction "P-15V_B-15'") (pintype "bidirectional"))
    )
    (net (code "39") (name "Net-(PCB1B-INL)") (class "Default")
      (node (ref "C6") (pin "+") (pinfunction "+_+") (pintype "passive"))
      (node (ref "PCB1") (pin "BINL") (pinfunction "INL_BINL") (pintype "bidirectional"))
    )
    (net (code "40") (name "Net-(PCB1C-INR)") (class "Default")
      (node (ref "C7") (pin "+") (pinfunction "+_+") (pintype "passive"))
      (node (ref "PCB1") (pin "BINR") (pinfunction "INR_BINR") (pintype "bidirectional"))
    )
    (net (code "41") (name "Net-(PCB1F-CV1)") (class "Default")
      (node (ref "PCB1") (pin "ACV1") (pinfunction "CV1_ACV1") (pintype "bidirectional"))
      (node (ref "PCB1") (pin "ACV1'") (pinfunction "CV1'_ACV1'") (pintype "bidirectional"))
      (node (ref "SA1") (pin "NO") (pinfunction "2_NO") (pintype "passive"))
      (node (ref "SA2") (pin "NO") (pinfunction "2_NO") (pintype "passive"))
    )
    (net (code "42") (name "Net-(PCB1F-CV2)") (class "Default")
      (node (ref "PCB1") (pin "ACV2") (pinfunction "CV2_ACV2") (pintype "bidirectional"))
      (node (ref "PCB1") (pin "ACV2'") (pinfunction "CV2'_ACV2'") (pintype "bidirectional"))
      (node (ref "SA1") (pin "NC") (pinfunction "1_NC") (pintype "passive"))
      (node (ref "SA2") (pin "NC") (pinfunction "1_NC") (pintype "passive"))
    )
    (net (code "43") (name "Net-(PCB1F-LFBK)") (class "Default")
      (node (ref "PCB1") (pin "ALFBK") (pinfunction "LFBK_ALFBK") (pintype "bidirectional"))
      (node (ref "PCB1") (pin "ALFBK'") (pinfunction "LFBK'_ALFBK'") (pintype "bidirectional"))
    )
    (net (code "44") (name "Net-(PCB1F-LMIX)") (class "Default")
      (node (ref "PCB1") (pin "ALMIX") (pinfunction "LMIX_ALMIX") (pintype "bidirectional"))
      (node (ref "PCB1") (pin "ALMIX'") (pinfunction "LMIX'_ALMIX'") (pintype "bidirectional"))
    )
    (net (code "45") (name "Net-(PCB1F-RFBK)") (class "Default")
      (node (ref "PCB1") (pin "ARFBK") (pinfunction "RFBK_ARFBK") (pintype "bidirectional"))
      (node (ref "PCB1") (pin "ARFBK'") (pinfunction "RFBK'_ARFBK'") (pintype "bidirectional"))
    )
    (net (code "46") (name "Net-(PCB1F-RMIX)") (class "Default")
      (node (ref "PCB1") (pin "ARMIX") (pinfunction "RMIX_ARMIX") (pintype "bidirectional"))
      (node (ref "PCB1") (pin "ARMIX'") (pinfunction "RMIX'_ARMIX'") (pintype "bidirectional"))
    )
    (net (code "47") (name "Net-(PCB1F-SENSE)") (class "Default")
      (node (ref "PCB1") (pin "BSENSE") (pinfunction "SENSE_BSENSE") (pintype "bidirectional"))
      (node (ref "PCB1") (pin "BSENSE'") (pinfunction "SENSE'_BSENSE'") (pintype "bidirectional"))
    )
    (net (code "48") (name "Net-(PCB1H-SMBCLK-PadASMBCLK')") (class "Default")
      (node (ref "PCB1") (pin "ASMBCLK") (pinfunction "SMBCLK_ASMBCLK") (pintype "bidirectional"))
      (node (ref "PCB1") (pin "ASMBCLK'") (pinfunction "SMBCLK_ASMBCLK'") (pintype "bidirectional"))
    )
    (net (code "49") (name "Net-(PCB1H-SMBDAT-PadASMBDAT')") (class "Default")
      (node (ref "PCB1") (pin "ASMBDAT") (pinfunction "SMBDAT_ASMBDAT") (pintype "bidirectional"))
      (node (ref "PCB1") (pin "ASMBDAT'") (pinfunction "SMBDAT_ASMBDAT'") (pintype "bidirectional"))
    )
    (net (code "50") (name "Net-(R1-Pad1)") (class "Default")
      (node (ref "R1") (pin "1") (pinfunction "1_1") (pintype "passive"))
      (node (ref "R19") (pin "1") (pinfunction "1_1") (pintype "passive"))
      (node (ref "R22") (pin "1") (pinfunction "1_1") (pintype "passive"))
      (node (ref "R32") (pin "2") (pinfunction "2_2") (pintype "passive"))
      (node (ref "R35") (pin "1") (pinfunction "1_1") (pintype "passive"))
    )
    (net (code "51") (name "Net-(R2-W)") (class "Default")
      (node (ref "R2") (pin "2") (pinfunction "W_2") (pintype "passive"))
      (node (ref "R6") (pin "1") (pinfunction "1_1") (pintype "passive"))
    )
    (net (code "52") (name "Net-(R3-W)") (class "Default")
      (node (ref "R3") (pin "2") (pinfunction "W_2") (pintype "passive"))
      (node (ref "R9") (pin "1") (pinfunction "1_1") (pintype "passive"))
    )
    (net (code "53") (name "Net-(R12-W)") (class "Default")
      (node (ref "R10") (pin "2") (pinfunction "2_2") (pintype "passive"))
      (node (ref "R12") (pin "2") (pinfunction "W_2") (pintype "passive"))
    )
    (net (code "54") (name "Net-(R14-W)") (class "Default")
      (node (ref "R14") (pin "2") (pinfunction "W_2") (pintype "passive"))
      (node (ref "R7") (pin "1") (pinfunction "1_1") (pintype "passive"))
    )
    (net (code "55") (name "Net-(R15-W)") (class "Default")
      (node (ref "R15") (pin "2") (pinfunction "W_2") (pintype "passive"))
      (node (ref "R8") (pin "2") (pinfunction "2_2") (pintype "passive"))
    )
    (net (code "56") (name "Net-(R20-Pad2)") (class "Default")
      (node (ref "R20") (pin "2") (pinfunction "2_2") (pintype "passive"))
      (node (ref "R29") (pin "1") (pinfunction "1_1") (pintype "passive"))
      (node (ref "VD3") (pin "C") (pinfunction "C_C") (pintype "passive"))
    )
    (net (code "57") (name "Net-(R21-Pad2)") (class "Default")
      (node (ref "R21") (pin "2") (pinfunction "2_2") (pintype "passive"))
      (node (ref "R30") (pin "1") (pinfunction "1_1") (pintype "passive"))
      (node (ref "VD4") (pin "A") (pinfunction "A_A") (pintype "passive"))
    )
    (net (code "58") (name "Net-(R41-CCW)") (class "Default")
      (node (ref "R41") (pin "1") (pinfunction "CCW_1") (pintype "passive"))
      (node (ref "R42") (pin "2") (pinfunction "2_2") (pintype "passive"))
    )
    (net (code "59") (name "Net-(R41-W)") (class "Default")
      (node (ref "R41") (pin "2") (pinfunction "W_2") (pintype "passive"))
      (node (ref "R44") (pin "1") (pinfunction "1_1") (pintype "passive"))
    )
    (net (code "60") (name "Net-(SA1-CM)") (class "Default")
      (node (ref "R8") (pin "1") (pinfunction "1_1") (pintype "passive"))
      (node (ref "SA1") (pin "C") (pinfunction "CM_C") (pintype "passive"))
    )
    (net (code "61") (name "Net-(SA2-CM)") (class "Default")
      (node (ref "R10") (pin "1") (pinfunction "1_1") (pintype "passive"))
      (node (ref "SA2") (pin "C") (pinfunction "CM_C") (pintype "passive"))
    )
    (net (code "62") (name "unconnected-(DA7B-SYM-Pad4)") (class "Default")
      (node (ref "DA7") (pin "4") (pinfunction "SYM_4") (pintype "output"))
    )
    (net (code "63") (name "unconnected-(DA8B-SYM-Pad4)") (class "Default")
      (node (ref "DA8") (pin "4") (pinfunction "SYM_4") (pintype "output"))
    )
  )
)
